# MCU.net
KiCad netlist of a schematic drawn in Altium Designer
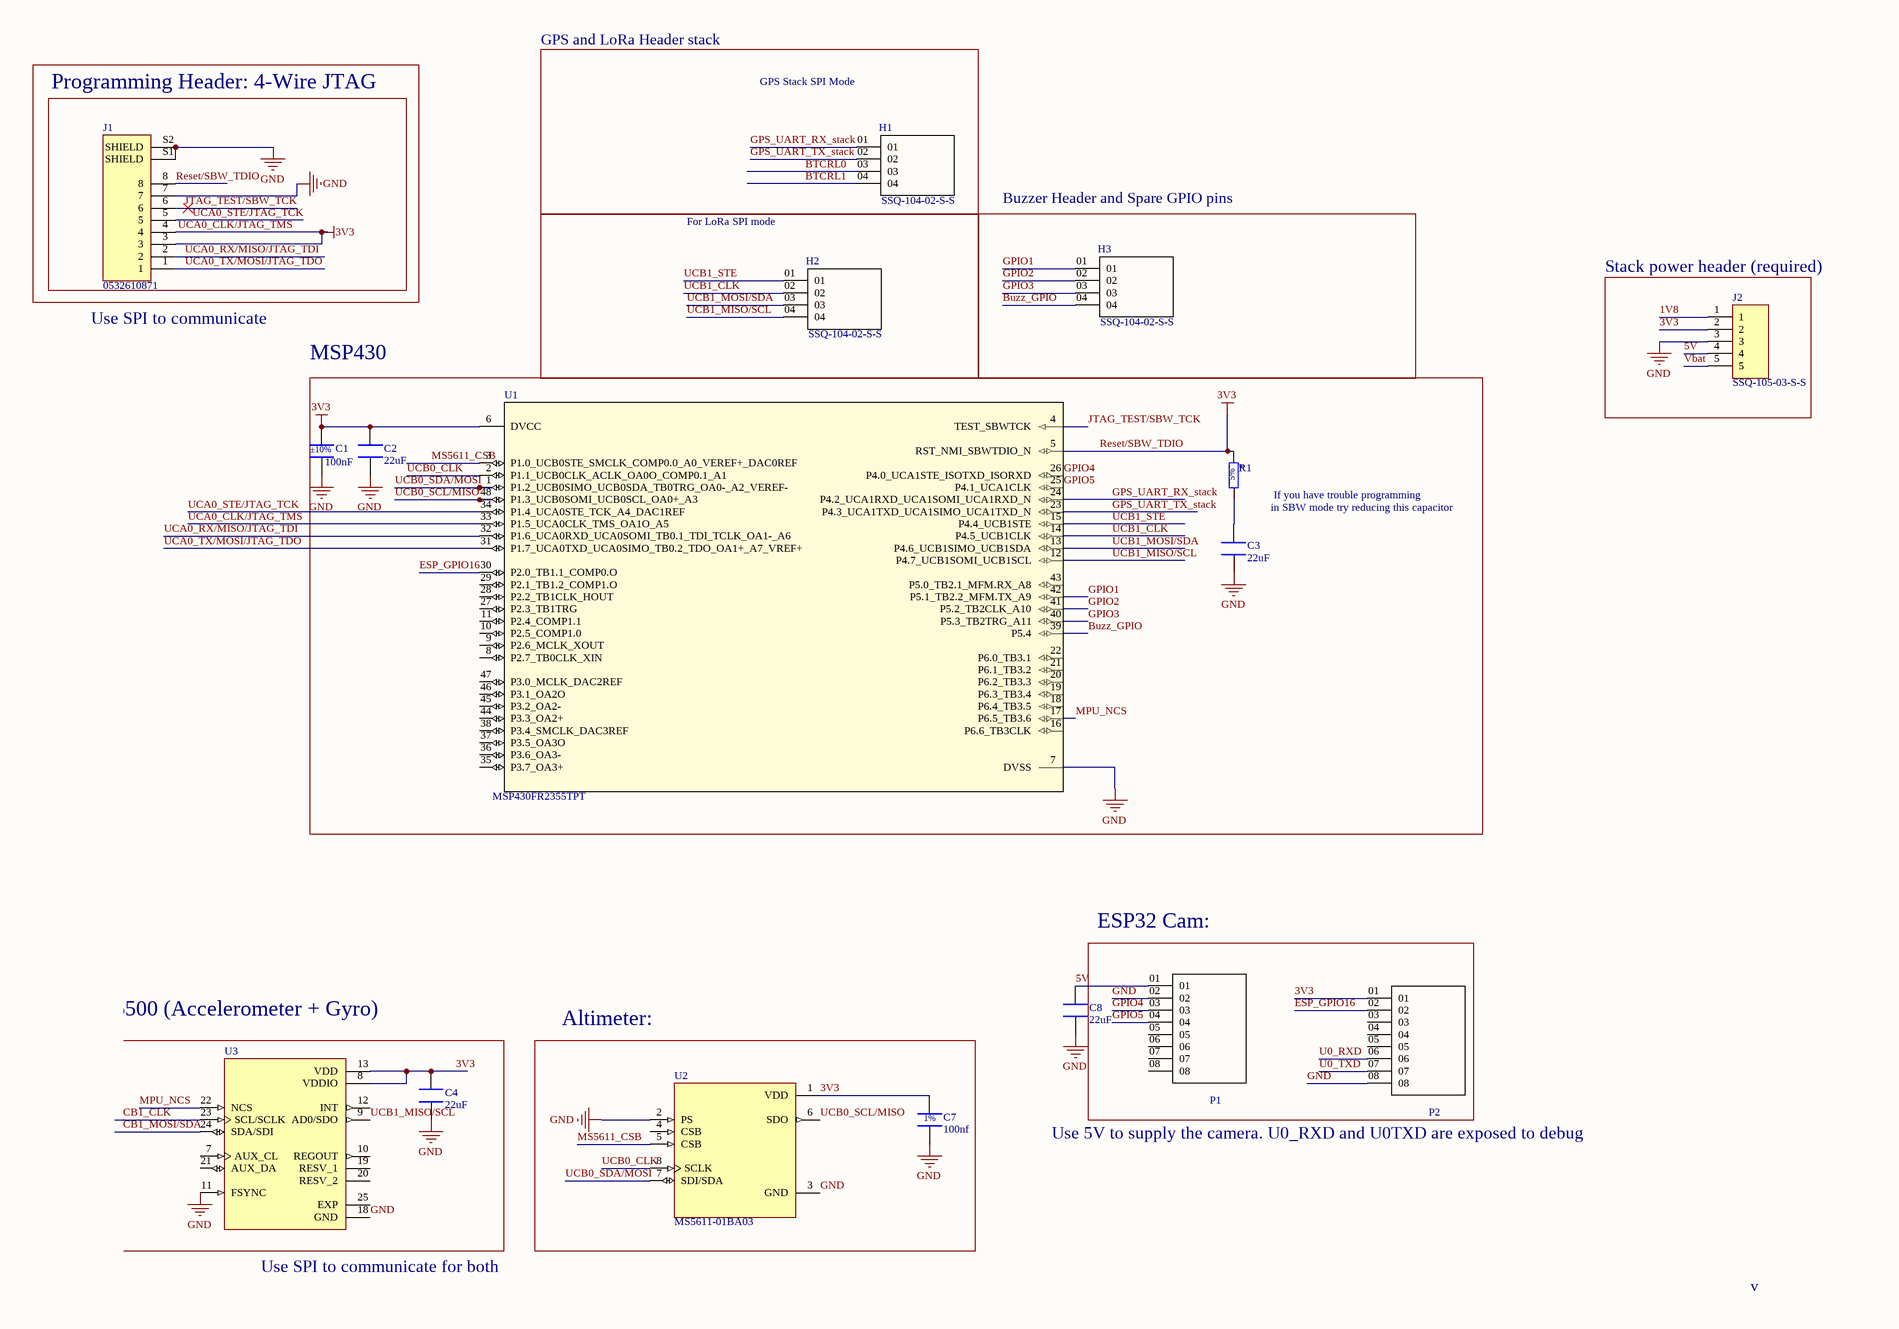
[diagram p0: MCU.SchDoc, left]
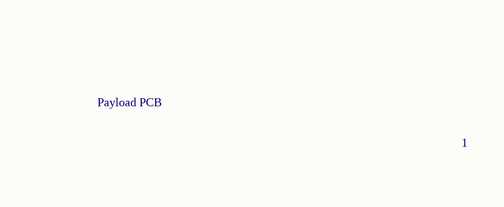
[diagram p1: MCU.SchDoc, right]

(export (version "E")
  (design (tool "Eeschema 10.0.6"))
  (components
    (comp (ref "C1")
      (value "100nF")
      (footprint "APSS Generic Components:CAPACITOR_0805_2012M-70N")
      (description "Generic Capacitor")
      (fields (field (name "TOLERANCE") "±10%") (field (name "MF PART NO.") "C0805C104K5RAC7800"))
      (libsource (lib "General Components") (part "Generic Capacitor"))
    )
    (comp (ref "C2")
      (value "22uF")
      (footprint "APSS Prototype Parts:CAPACITOR_0805_2012M-70N")
      (description "Passive - Capacitor, X5R, 22uF Max, 6.3V, 0805 (2012 Metric), ±20%, -55°C ~ 85°C. 8.8uF @ 5V")
      (fields (field (name "TOLERANCE") "±20%") (field (name "MF PART NO.") "C0805C226M9PACTU"))
      (libsource (lib "APSS Prototype Parts") (part "C0805C226M9PACTU"))
    )
    (comp (ref "C3")
      (value "22uF")
      (footprint "APSS Prototype Parts:CAPACITOR_0805_2012M-70N")
      (description "Passive - Capacitor, X5R, 22uF Max, 6.3V, 0805 (2012 Metric), ±20%, -55°C ~ 85°C. 8.8uF @ 5V")
      (fields (field (name "TOLERANCE") "±20%") (field (name "MF PART NO.") "C0805C226M9PACTU"))
      (libsource (lib "APSS Prototype Parts") (part "C0805C226M9PACTU"))
    )
    (comp (ref "C4")
      (value "22uF")
      (footprint "APSS Prototype Parts:CAPACITOR_0805_2012M-70N")
      (description "Passive - Capacitor, X5R, 22uF Max, 6.3V, 0805 (2012 Metric), ±20%, -55°C ~ 85°C. 8.8uF @ 5V")
      (fields (field (name "TOLERANCE") "±20%") (field (name "MF PART NO.") "C0805C226M9PACTU"))
      (libsource (lib "APSS Prototype Parts") (part "C0805C226M9PACTU"))
    )
    (comp (ref "C7")
      (value "100nf")
      (footprint "APSS Prototype Parts:CAPACITOR_0402_1005M_55N")
      (description "Passive - Capacitor Series, C0G, 5pF ~ 1nF, 50V, 0402 (1005 Metric), ±1%, -55°C ~ 125°C")
      (fields (field (name "TOLERANCE") "±1%") (field (name "APSS STANDARD PART") "APSS Standard"))
      (libsource (lib "APSS Prototype Parts") (part "GCM1555CxxxxxF Series"))
    )
    (comp (ref "C8")
      (value "22uF")
      (footprint "APSS Prototype Parts:CAPACITOR_0805_2012M-70N")
      (description "Passive - Capacitor, X5R, 22uF Max, 6.3V, 0805 (2012 Metric), ±20%, -55°C ~ 85°C. 8.8uF @ 5V")
      (fields (field (name "TOLERANCE") "±20%") (field (name "MF PART NO.") "C0805C226M9PACTU"))
      (libsource (lib "APSS Prototype Parts") (part "C0805C226M9PACTU"))
    )
    (comp (ref "H1")
      (value "SSQ-104-02-S-S")
      (footprint "*SAMTEC_SSQ-104-02-S-S_SSQ-104-02-S-S(Primary)")
      (libsource (lib "SSQ-104-02-S-S") (part "SSQ-104-02-S-S"))
    )
    (comp (ref "H2")
      (value "SSQ-104-02-S-S")
      (footprint "*SAMTEC_SSQ-104-02-S-S_SSQ-104-02-S-S(Primary)")
      (libsource (lib "SSQ-104-02-S-S") (part "SSQ-104-02-S-S"))
    )
    (comp (ref "H3")
      (value "SSQ-104-02-S-S")
      (footprint "*SAMTEC_SSQ-104-02-S-S_SSQ-104-02-S-S(Primary)")
      (libsource (lib "SSQ-104-02-S-S") (part "SSQ-104-02-S-S"))
    )
    (comp (ref "J1")
      (value "0532610871")
      (footprint "MOLEX_0532610871")
      (description "Picoblade Connector, 8 Circuit Single Row, Right Angle Surface Mount SMT PCB")
      (fields (field (name "MF") "Molex"))
      (libsource (lib "0532610871") (part "0532610871"))
    )
    (comp (ref "J2")
      (value "SSQ-105-03-S-S")
      (footprint "SAMTEC_SSQ-105-03-S-S")
      (fields (field (name "MF") "{'manufacturer': u'Samtec Inc.'}"))
      (libsource (lib "SSQ-105-03-S-S") (part "SSQ-105-03-S-S"))
    )
    (comp (ref "P1")
      (value "SSQ-108-01-F-S-LL")
      (footprint "*SAMTEC_SSQ-108-01-F-S-LL_SSQ-108-01-F-S-LL(Primary)")
      (libsource (lib "SSQ-108-01-F-S-LL") (part "SSQ-108-01-F-S-LL"))
    )
    (comp (ref "P2")
      (value "SSQ-108-01-F-S-LL")
      (footprint "*SAMTEC_SSQ-108-01-F-S-LL_SSQ-108-01-F-S-LL(Primary)")
      (libsource (lib "SSQ-108-01-F-S-LL") (part "SSQ-108-01-F-S-LL"))
    )
    (comp (ref "R1")
      (value "*")
      (footprint "APSS Prototype Parts:Resistor_0805_2012M-50N")
      (fields
        (field (name "TOLERANCE") "5%")
        (field (name "POWER") "1/8W")
        (field (name "ALTIUM_VALUE") "*")
        (field (name "APSS STANDARD PART") "APSS Standard")
      )
      (libsource (lib "APSS Prototype Parts") (part "RMCF0805JT Series"))
    )
    (comp (ref "U1")
      (value "MSP430FR2355TPT")
      (footprint "PT0048A_L")
      (fields (field (name "APSS STANDARD PART") "APSS Standard"))
      (libsource (lib "MSP430") (part "MSP430FR2355IPT"))
    )
    (comp (ref "U2")
      (value "MS5611-01BA03")
      (footprint "SON125P500X300X100-8N")
      (description "Pressure Sensor 0.15PSI ~ 17.4PSI (1kPa ~ 120kPa) Absolute - 24 b 8-SMD")
      (fields (field (name "MF") "TE Connectivity"))
      (libsource (lib "MS5611-01BA03") (part "MS5611-01BA03"))
    )
    (comp (ref "U3")
      (value "~")
      (footprint "QFN40P300X300X95-25N")
      (description "MotionTracking Device Digital Output 1.8V 24-Pin QFN EP T/R")
      (fields (field (name "MF") "TDK InvenSense") (field (name "MP") "MPU-6500"))
      (libsource (lib "MPU-6500") (part "MPU-6500"))
    )
  )
  (nets
    (net (code "1") (name "/1V8") (class "Default")
      (node (ref "J2") (pin "1") (pinfunction "1_1") (pintype "passive"))
    )
    (net (code "2") (name "/5V") (class "Default")
      (node (ref "C8") (pin "2") (pinfunction "2_2") (pintype "passive"))
      (node (ref "J2") (pin "4") (pinfunction "4_4") (pintype "passive"))
      (node (ref "P1") (pin "01") (pinfunction "01_01") (pintype "passive"))
    )
    (net (code "3") (name "/BTCRL0") (class "Default")
      (node (ref "H1") (pin "03") (pinfunction "03_03") (pintype "passive"))
    )
    (net (code "4") (name "/BTCRL1") (class "Default")
      (node (ref "H1") (pin "04") (pinfunction "04_04") (pintype "passive"))
    )
    (net (code "5") (name "/Buzz_GPIO") (class "Default")
      (node (ref "H3") (pin "04") (pinfunction "04_04") (pintype "passive"))
      (node (ref "U1") (pin "39") (pinfunction "P5.4_39") (pintype "bidirectional"))
    )
    (net (code "6") (name "/ESP_GPIO16") (class "Default")
      (node (ref "P2") (pin "02") (pinfunction "02_02") (pintype "passive"))
      (node (ref "U1") (pin "30") (pinfunction "P2.0_TB1.1_COMP0.O_30") (pintype "bidirectional"))
    )
    (net (code "7") (name "/GPIO1") (class "Default")
      (node (ref "H3") (pin "01") (pinfunction "01_01") (pintype "passive"))
      (node (ref "U1") (pin "42") (pinfunction "P5.1_TB2.2_MFM.TX_A9_42") (pintype "bidirectional"))
    )
    (net (code "8") (name "/GPIO2") (class "Default")
      (node (ref "H3") (pin "02") (pinfunction "02_02") (pintype "passive"))
      (node (ref "U1") (pin "41") (pinfunction "P5.2_TB2CLK_A10_41") (pintype "bidirectional"))
    )
    (net (code "9") (name "/GPIO3") (class "Default")
      (node (ref "H3") (pin "03") (pinfunction "03_03") (pintype "passive"))
      (node (ref "U1") (pin "40") (pinfunction "P5.3_TB2TRG_A11_40") (pintype "bidirectional"))
    )
    (net (code "10") (name "/GPIO4") (class "Default")
      (node (ref "P1") (pin "03") (pinfunction "03_03") (pintype "passive"))
      (node (ref "U1") (pin "26") (pinfunction "P4.0_UCA1STE_ISOTXD_ISORXD_26") (pintype "bidirectional"))
    )
    (net (code "11") (name "/GPIO5") (class "Default")
      (node (ref "P1") (pin "04") (pinfunction "04_04") (pintype "passive"))
      (node (ref "U1") (pin "25") (pinfunction "P4.1_UCA1CLK_25") (pintype "bidirectional"))
    )
    (net (code "12") (name "/GPS_UART_RX_stack") (class "Default")
      (node (ref "H1") (pin "01") (pinfunction "01_01") (pintype "passive"))
      (node (ref "U1") (pin "24") (pinfunction "P4.2_UCA1RXD_UCA1SOMI_UCA1RXD_N_24") (pintype "bidirectional"))
    )
    (net (code "13") (name "/GPS_UART_TX_stack") (class "Default")
      (node (ref "H1") (pin "02") (pinfunction "02_02") (pintype "passive"))
      (node (ref "U1") (pin "23") (pinfunction "P4.3_UCA1TXD_UCA1SIMO_UCA1TXD_N_23") (pintype "bidirectional"))
    )
    (net (code "14") (name "/JTAG_TEST{slash}SBW_TCK") (class "Default")
      (node (ref "J1") (pin "6") (pinfunction "6_6") (pintype "passive"))
      (node (ref "U1") (pin "4") (pinfunction "TEST_SBWTCK_4") (pintype "input"))
    )
    (net (code "15") (name "/MPU_NCS") (class "Default")
      (node (ref "U1") (pin "17") (pinfunction "P6.5_TB3.6_17") (pintype "bidirectional"))
      (node (ref "U3") (pin "22") (pinfunction "NCS_22") (pintype "input"))
    )
    (net (code "16") (name "/MS5611_CSB") (class "Default")
      (node (ref "U1") (pin "3") (pinfunction "P1.0_UCB0STE_SMCLK_COMP0.0_A0_VEREF+_DAC0REF_3") (pintype "bidirectional"))
      (node (ref "U2") (pin "5") (pinfunction "CSB_5") (pintype "input"))
    )
    (net (code "17") (name "/U0_RXD") (class "Default")
      (node (ref "P2") (pin "06") (pinfunction "06_06") (pintype "passive"))
    )
    (net (code "18") (name "/U0_TXD") (class "Default")
      (node (ref "P2") (pin "07") (pinfunction "07_07") (pintype "passive"))
    )
    (net (code "19") (name "/UCA0_RX{slash}MISO{slash}JTAG_TDI") (class "Default")
      (node (ref "J1") (pin "2") (pinfunction "2_2") (pintype "passive"))
      (node (ref "U1") (pin "32") (pinfunction "P1.6_UCA0RXD_UCA0SOMI_TB0.1_TDI_TCLK_OA1-_A6_32") (pintype "bidirectional"))
    )
    (net (code "20") (name "/UCA0_STE{slash}JTAG_TCK") (class "Default")
      (node (ref "J1") (pin "5") (pinfunction "5_5") (pintype "passive"))
      (node (ref "U1") (pin "34") (pinfunction "P1.4_UCA0STE_TCK_A4_DAC1REF_34") (pintype "bidirectional"))
    )
    (net (code "21") (name "/UCA0_TX{slash}MOSI{slash}JTAG_TDO") (class "Default")
      (node (ref "J1") (pin "1") (pinfunction "1_1") (pintype "passive"))
      (node (ref "U1") (pin "31") (pinfunction "P1.7_UCA0TXD_UCA0SIMO_TB0.2_TDO_OA1+_A7_VREF+_31") (pintype "bidirectional"))
    )
    (net (code "22") (name "/UCB0_CLK") (class "Default")
      (node (ref "U1") (pin "2") (pinfunction "P1.1_UCB0CLK_ACLK_OA0O_COMP0.1_A1_2") (pintype "bidirectional"))
      (node (ref "U2") (pin "8") (pinfunction "SCLK_8") (pintype "input"))
    )
    (net (code "23") (name "/UCB0_SCL{slash}MISO") (class "Default")
      (node (ref "U1") (pin "48") (pinfunction "P1.3_UCB0SOMI_UCB0SCL_OA0+_A3_48") (pintype "bidirectional"))
      (node (ref "U2") (pin "6") (pinfunction "SDO_6") (pintype "output"))
    )
    (net (code "24") (name "/UCB0_SDA{slash}MOSI") (class "Default")
      (node (ref "U1") (pin "1") (pinfunction "P1.2_UCB0SIMO_UCB0SDA_TB0TRG_OA0-_A2_VEREF-_1") (pintype "bidirectional"))
      (node (ref "U2") (pin "7") (pinfunction "SDI/SDA_7") (pintype "bidirectional"))
    )
    (net (code "25") (name "/UCB1_CLK") (class "Default")
      (node (ref "H2") (pin "02") (pinfunction "02_02") (pintype "passive"))
      (node (ref "U1") (pin "14") (pinfunction "P4.5_UCB1CLK_14") (pintype "bidirectional"))
      (node (ref "U3") (pin "23") (pinfunction "SCL/SCLK_23") (pintype "input"))
    )
    (net (code "26") (name "/UCB1_MISO{slash}SCL") (class "Default")
      (node (ref "H2") (pin "04") (pinfunction "04_04") (pintype "passive"))
      (node (ref "U1") (pin "12") (pinfunction "P4.7_UCB1SOMI_UCB1SCL_12") (pintype "bidirectional"))
      (node (ref "U3") (pin "9") (pinfunction "AD0/SDO_9") (pintype "output"))
    )
    (net (code "27") (name "/UCB1_MOSI{slash}SDA") (class "Default")
      (node (ref "H2") (pin "03") (pinfunction "03_03") (pintype "passive"))
      (node (ref "U1") (pin "13") (pinfunction "P4.6_UCB1SIMO_UCB1SDA_13") (pintype "bidirectional"))
      (node (ref "U3") (pin "24") (pinfunction "SDA/SDI_24") (pintype "bidirectional"))
    )
    (net (code "28") (name "/UCB1_STE") (class "Default")
      (node (ref "H2") (pin "01") (pinfunction "01_01") (pintype "passive"))
      (node (ref "U1") (pin "15") (pinfunction "P4.4_UCB1STE_15") (pintype "bidirectional"))
    )
    (net (code "29") (name "/Vbat") (class "Default")
      (node (ref "J2") (pin "5") (pinfunction "5_5") (pintype "passive"))
    )
    (net (code "30") (name "3V3") (class "Default")
      (node (ref "C1") (pin "2") (pinfunction "2_2") (pintype "passive"))
      (node (ref "C2") (pin "2") (pinfunction "2_2") (pintype "passive"))
      (node (ref "C4") (pin "2") (pinfunction "2_2") (pintype "passive"))
      (node (ref "C7") (pin "2") (pinfunction "2_2") (pintype "passive"))
      (node (ref "J1") (pin "3") (pinfunction "3_3") (pintype "passive"))
      (node (ref "J1") (pin "4") (pinfunction "4_4") (pintype "passive"))
      (node (ref "J1") (pin "8") (pinfunction "8_8") (pintype "passive"))
      (node (ref "J2") (pin "2") (pinfunction "2_2") (pintype "passive"))
      (node (ref "P2") (pin "01") (pinfunction "01_01") (pintype "passive"))
      (node (ref "R1") (pin "2") (pinfunction "2_2") (pintype "passive"))
      (node (ref "U1") (pin "33") (pinfunction "P1.5_UCA0CLK_TMS_OA1O_A5_33") (pintype "bidirectional"))
      (node (ref "U1") (pin "5") (pinfunction "RST_NMI_SBWTDIO_N_5") (pintype "bidirectional"))
      (node (ref "U1") (pin "6") (pinfunction "DVCC_6") (pintype "power_in"))
      (node (ref "U2") (pin "1") (pinfunction "VDD_1") (pintype "power_in"))
      (node (ref "U3") (pin "13") (pinfunction "VDD_13") (pintype "power_in"))
      (node (ref "U3") (pin "8") (pinfunction "VDDIO_8") (pintype "power_in"))
    )
    (net (code "31") (name "GND") (class "Default")
      (node (ref "C1") (pin "1") (pinfunction "1_1") (pintype "passive"))
      (node (ref "C2") (pin "1") (pinfunction "1_1") (pintype "passive"))
      (node (ref "C3") (pin "1") (pinfunction "1_1") (pintype "passive"))
      (node (ref "C4") (pin "1") (pinfunction "1_1") (pintype "passive"))
      (node (ref "C7") (pin "1") (pinfunction "1_1") (pintype "passive"))
      (node (ref "C8") (pin "1") (pinfunction "1_1") (pintype "passive"))
      (node (ref "J1") (pin "7") (pinfunction "7_7") (pintype "passive"))
      (node (ref "J1") (pin "S1") (pinfunction "SHIELD_S1") (pintype "passive"))
      (node (ref "J1") (pin "S2") (pinfunction "SHIELD_S2") (pintype "passive"))
      (node (ref "J2") (pin "3") (pinfunction "3_3") (pintype "passive"))
      (node (ref "P1") (pin "02") (pinfunction "02_02") (pintype "passive"))
      (node (ref "P2") (pin "08") (pinfunction "08_08") (pintype "passive"))
      (node (ref "U1") (pin "7") (pinfunction "DVSS_7") (pintype "power_in"))
      (node (ref "U2") (pin "2") (pinfunction "PS_2") (pintype "input"))
      (node (ref "U2") (pin "3") (pinfunction "GND_3") (pintype "power_in"))
      (node (ref "U3") (pin "11") (pinfunction "FSYNC_11") (pintype "input"))
      (node (ref "U3") (pin "18") (pinfunction "GND_18") (pintype "power_in"))
    )
    (net (code "32") (name "Net-(C3-Pad2)") (class "Default")
      (node (ref "C3") (pin "2") (pinfunction "2_2") (pintype "passive"))
      (node (ref "R1") (pin "1") (pinfunction "1_1") (pintype "passive"))
    )
    (net (code "33") (name "unconnected-(P1-Pad05)") (class "Default")
      (node (ref "P1") (pin "05") (pinfunction "05_05") (pintype "passive"))
    )
    (net (code "34") (name "unconnected-(P1-Pad06)") (class "Default")
      (node (ref "P1") (pin "06") (pinfunction "06_06") (pintype "passive"))
    )
    (net (code "35") (name "unconnected-(P1-Pad07)") (class "Default")
      (node (ref "P1") (pin "07") (pinfunction "07_07") (pintype "passive"))
    )
    (net (code "36") (name "unconnected-(P1-Pad08)") (class "Default")
      (node (ref "P1") (pin "08") (pinfunction "08_08") (pintype "passive"))
    )
    (net (code "37") (name "unconnected-(P2-Pad03)") (class "Default")
      (node (ref "P2") (pin "03") (pinfunction "03_03") (pintype "passive"))
    )
    (net (code "38") (name "unconnected-(P2-Pad04)") (class "Default")
      (node (ref "P2") (pin "04") (pinfunction "04_04") (pintype "passive"))
    )
    (net (code "39") (name "unconnected-(P2-Pad05)") (class "Default")
      (node (ref "P2") (pin "05") (pinfunction "05_05") (pintype "passive"))
    )
    (net (code "40") (name "unconnected-(U1-P2.1_TB1.2_COMP1.O-Pad29)") (class "Default")
      (node (ref "U1") (pin "29") (pinfunction "P2.1_TB1.2_COMP1.O_29") (pintype "bidirectional"))
    )
    (net (code "41") (name "unconnected-(U1-P2.2_TB1CLK_HOUT-Pad28)") (class "Default")
      (node (ref "U1") (pin "28") (pinfunction "P2.2_TB1CLK_HOUT_28") (pintype "bidirectional"))
    )
    (net (code "42") (name "unconnected-(U1-P2.3_TB1TRG-Pad27)") (class "Default")
      (node (ref "U1") (pin "27") (pinfunction "P2.3_TB1TRG_27") (pintype "bidirectional"))
    )
    (net (code "43") (name "unconnected-(U1-P2.4_COMP1.1-Pad11)") (class "Default")
      (node (ref "U1") (pin "11") (pinfunction "P2.4_COMP1.1_11") (pintype "bidirectional"))
    )
    (net (code "44") (name "unconnected-(U1-P2.5_COMP1.0-Pad10)") (class "Default")
      (node (ref "U1") (pin "10") (pinfunction "P2.5_COMP1.0_10") (pintype "bidirectional"))
    )
    (net (code "45") (name "unconnected-(U1-P2.6_MCLK_XOUT-Pad9)") (class "Default")
      (node (ref "U1") (pin "9") (pinfunction "P2.6_MCLK_XOUT_9") (pintype "bidirectional"))
    )
    (net (code "46") (name "unconnected-(U1-P2.7_TB0CLK_XIN-Pad8)") (class "Default")
      (node (ref "U1") (pin "8") (pinfunction "P2.7_TB0CLK_XIN_8") (pintype "bidirectional"))
    )
    (net (code "47") (name "unconnected-(U1-P3.0_MCLK_DAC2REF-Pad47)") (class "Default")
      (node (ref "U1") (pin "47") (pinfunction "P3.0_MCLK_DAC2REF_47") (pintype "bidirectional"))
    )
    (net (code "48") (name "unconnected-(U1-P3.1_OA2O-Pad46)") (class "Default")
      (node (ref "U1") (pin "46") (pinfunction "P3.1_OA2O_46") (pintype "bidirectional"))
    )
    (net (code "49") (name "unconnected-(U1-P3.2_OA2--Pad45)") (class "Default")
      (node (ref "U1") (pin "45") (pinfunction "P3.2_OA2-_45") (pintype "bidirectional"))
    )
    (net (code "50") (name "unconnected-(U1-P3.3_OA2+-Pad44)") (class "Default")
      (node (ref "U1") (pin "44") (pinfunction "P3.3_OA2+_44") (pintype "bidirectional"))
    )
    (net (code "51") (name "unconnected-(U1-P3.4_SMCLK_DAC3REF-Pad38)") (class "Default")
      (node (ref "U1") (pin "38") (pinfunction "P3.4_SMCLK_DAC3REF_38") (pintype "bidirectional"))
    )
    (net (code "52") (name "unconnected-(U1-P3.5_OA3O-Pad37)") (class "Default")
      (node (ref "U1") (pin "37") (pinfunction "P3.5_OA3O_37") (pintype "bidirectional"))
    )
    (net (code "53") (name "unconnected-(U1-P3.6_OA3--Pad36)") (class "Default")
      (node (ref "U1") (pin "36") (pinfunction "P3.6_OA3-_36") (pintype "bidirectional"))
    )
    (net (code "54") (name "unconnected-(U1-P3.7_OA3+-Pad35)") (class "Default")
      (node (ref "U1") (pin "35") (pinfunction "P3.7_OA3+_35") (pintype "bidirectional"))
    )
    (net (code "55") (name "unconnected-(U1-P5.0_TB2.1_MFM.RX_A8-Pad43)") (class "Default")
      (node (ref "U1") (pin "43") (pinfunction "P5.0_TB2.1_MFM.RX_A8_43") (pintype "bidirectional"))
    )
    (net (code "56") (name "unconnected-(U1-P6.0_TB3.1-Pad22)") (class "Default")
      (node (ref "U1") (pin "22") (pinfunction "P6.0_TB3.1_22") (pintype "bidirectional"))
    )
    (net (code "57") (name "unconnected-(U1-P6.1_TB3.2-Pad21)") (class "Default")
      (node (ref "U1") (pin "21") (pinfunction "P6.1_TB3.2_21") (pintype "bidirectional"))
    )
    (net (code "58") (name "unconnected-(U1-P6.2_TB3.3-Pad20)") (class "Default")
      (node (ref "U1") (pin "20") (pinfunction "P6.2_TB3.3_20") (pintype "bidirectional"))
    )
    (net (code "59") (name "unconnected-(U1-P6.3_TB3.4-Pad19)") (class "Default")
      (node (ref "U1") (pin "19") (pinfunction "P6.3_TB3.4_19") (pintype "bidirectional"))
    )
    (net (code "60") (name "unconnected-(U1-P6.4_TB3.5-Pad18)") (class "Default")
      (node (ref "U1") (pin "18") (pinfunction "P6.4_TB3.5_18") (pintype "bidirectional"))
    )
    (net (code "61") (name "unconnected-(U1-P6.6_TB3CLK-Pad16)") (class "Default")
      (node (ref "U1") (pin "16") (pinfunction "P6.6_TB3CLK_16") (pintype "bidirectional"))
    )
    (net (code "62") (name "unconnected-(U2-CSB-Pad4)") (class "Default")
      (node (ref "U2") (pin "4") (pinfunction "CSB_4") (pintype "input"))
    )
    (net (code "63") (name "unconnected-(U3-AUX_CL-Pad7)") (class "Default")
      (node (ref "U3") (pin "7") (pinfunction "AUX_CL_7") (pintype "input"))
    )
    (net (code "64") (name "unconnected-(U3-AUX_DA-Pad21)") (class "Default")
      (node (ref "U3") (pin "21") (pinfunction "AUX_DA_21") (pintype "bidirectional"))
    )
    (net (code "65") (name "unconnected-(U3-EXP-Pad25)") (class "Default")
      (node (ref "U3") (pin "25") (pinfunction "EXP_25") (pintype "passive"))
    )
    (net (code "66") (name "unconnected-(U3-INT-Pad12)") (class "Default")
      (node (ref "U3") (pin "12") (pinfunction "INT_12") (pintype "output"))
    )
    (net (code "67") (name "unconnected-(U3-REGOUT-Pad10)") (class "Default")
      (node (ref "U3") (pin "10") (pinfunction "REGOUT_10") (pintype "output"))
    )
    (net (code "68") (name "unconnected-(U3-RESV_1-Pad19)") (class "Default")
      (node (ref "U3") (pin "19") (pinfunction "RESV_1_19") (pintype "passive"))
    )
    (net (code "69") (name "unconnected-(U3-RESV_2-Pad20)") (class "Default")
      (node (ref "U3") (pin "20") (pinfunction "RESV_2_20") (pintype "passive"))
    )
  )
)
